# MCU_ZC-ST4X-A005A.net
KiCad netlist of a schematic drawn in Altium Designer
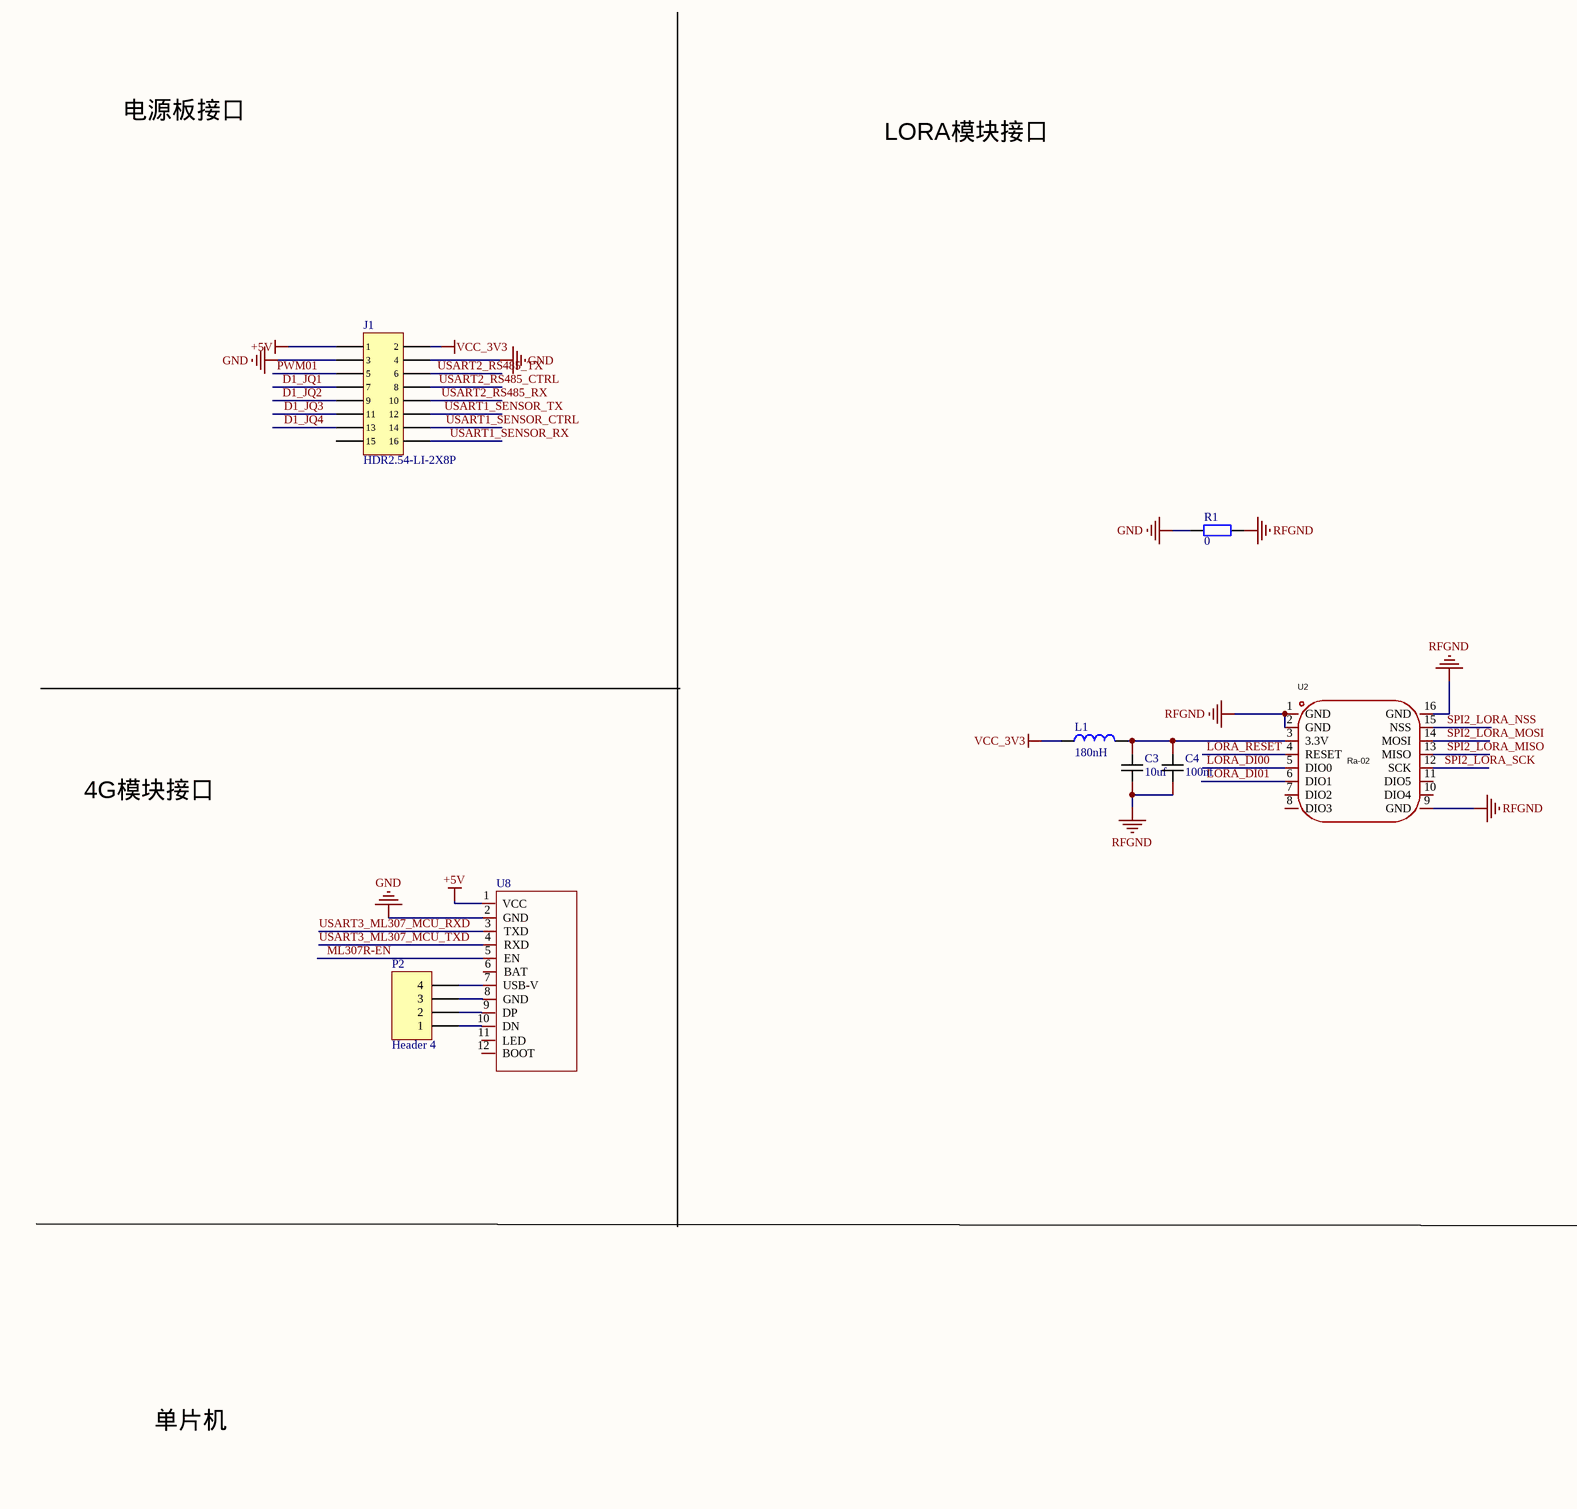
[diagram p0: MCU(ZC-ST4X-A005A).SchDoc, top left]
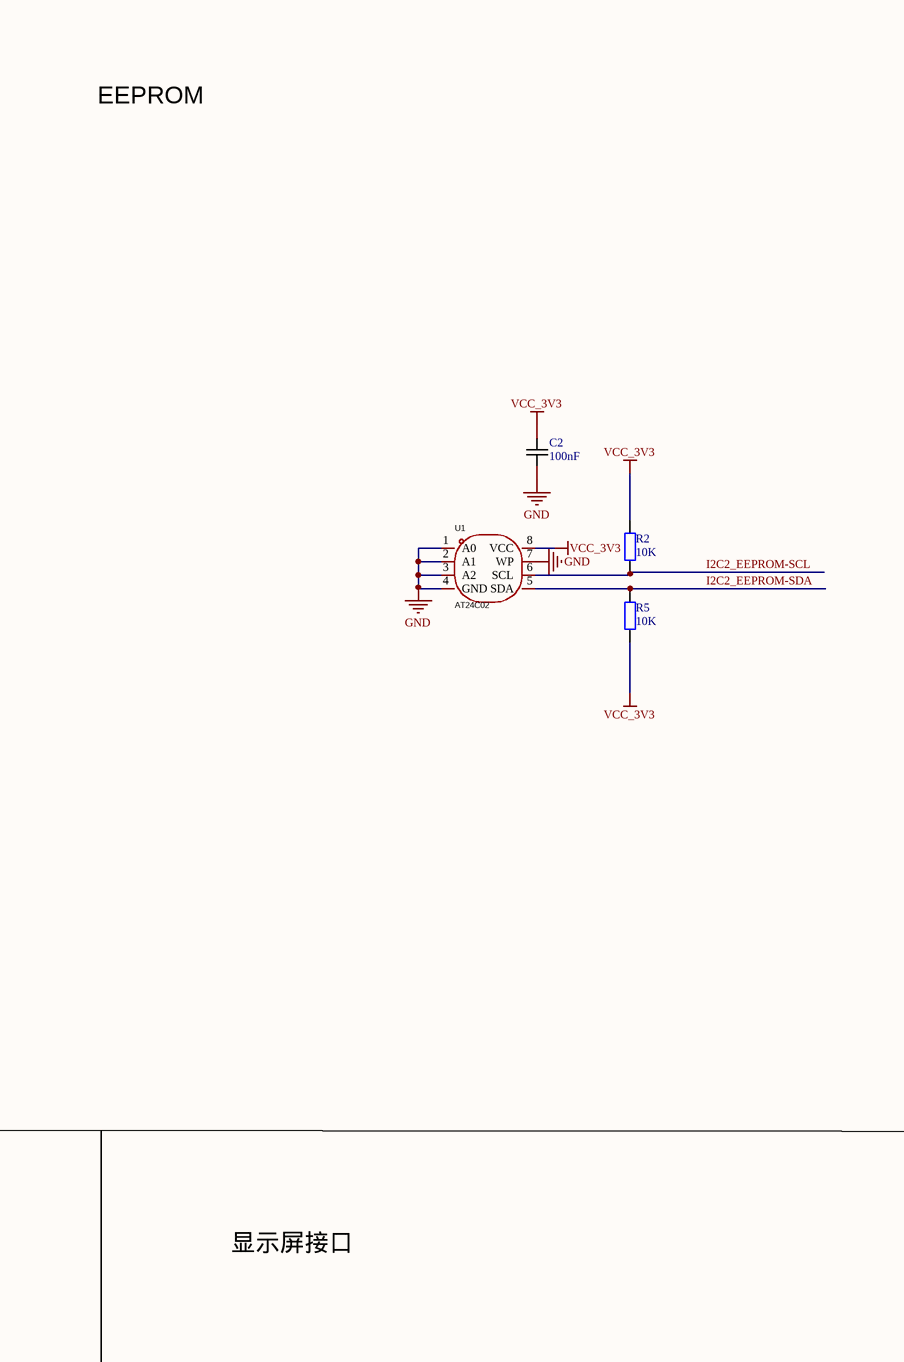
[diagram p1: MCU(ZC-ST4X-A005A).SchDoc, top middle]
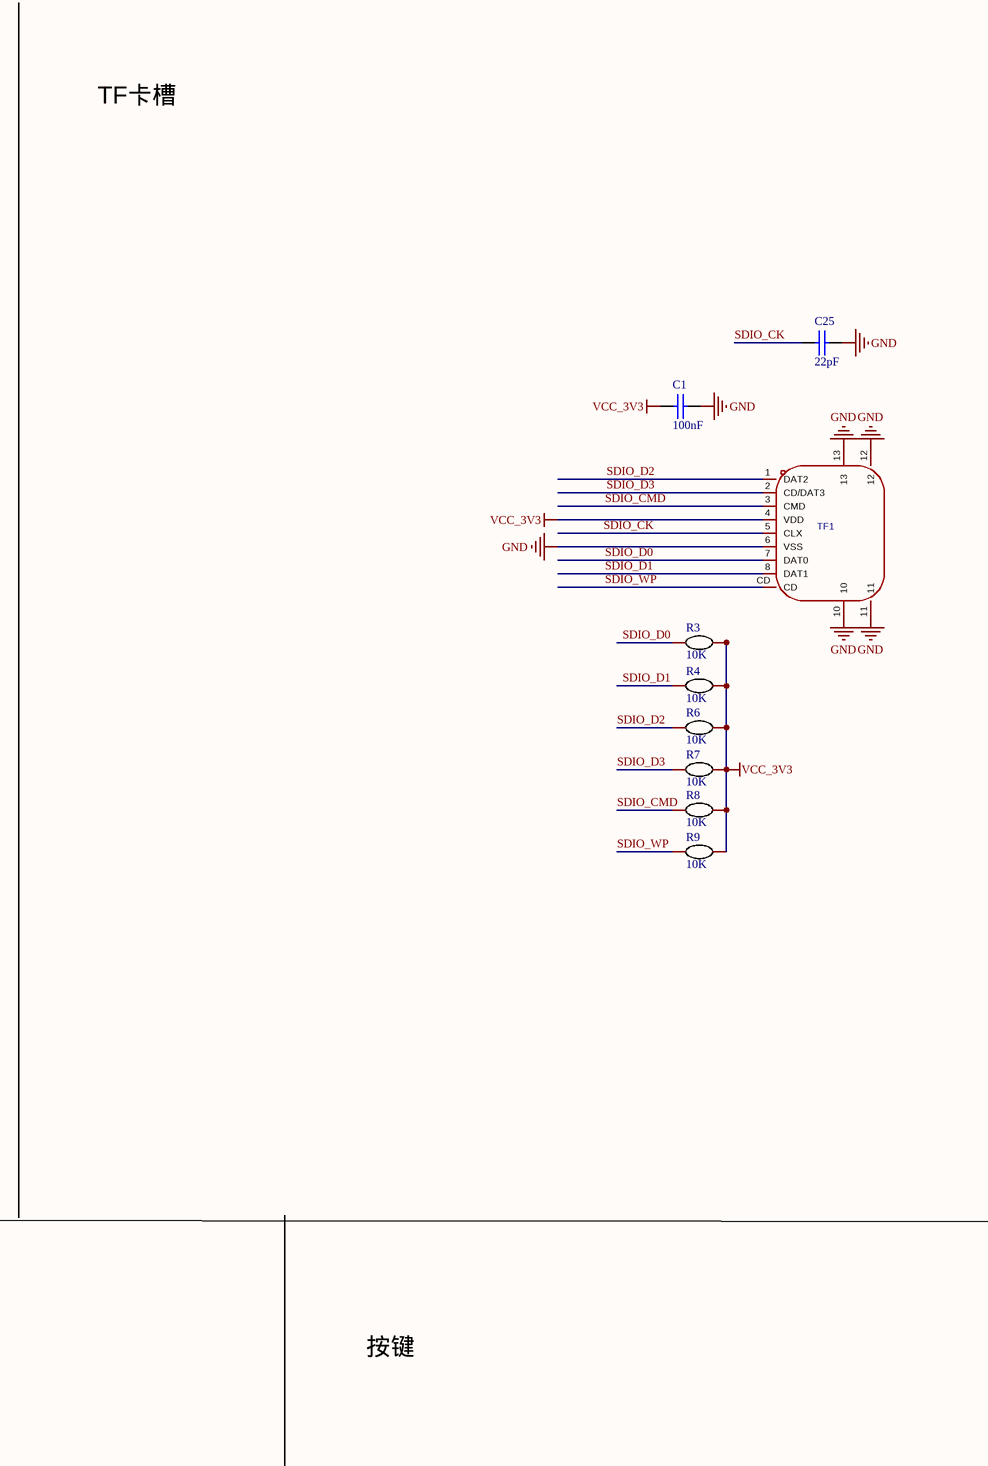
[diagram p2: MCU(ZC-ST4X-A005A).SchDoc, top right]
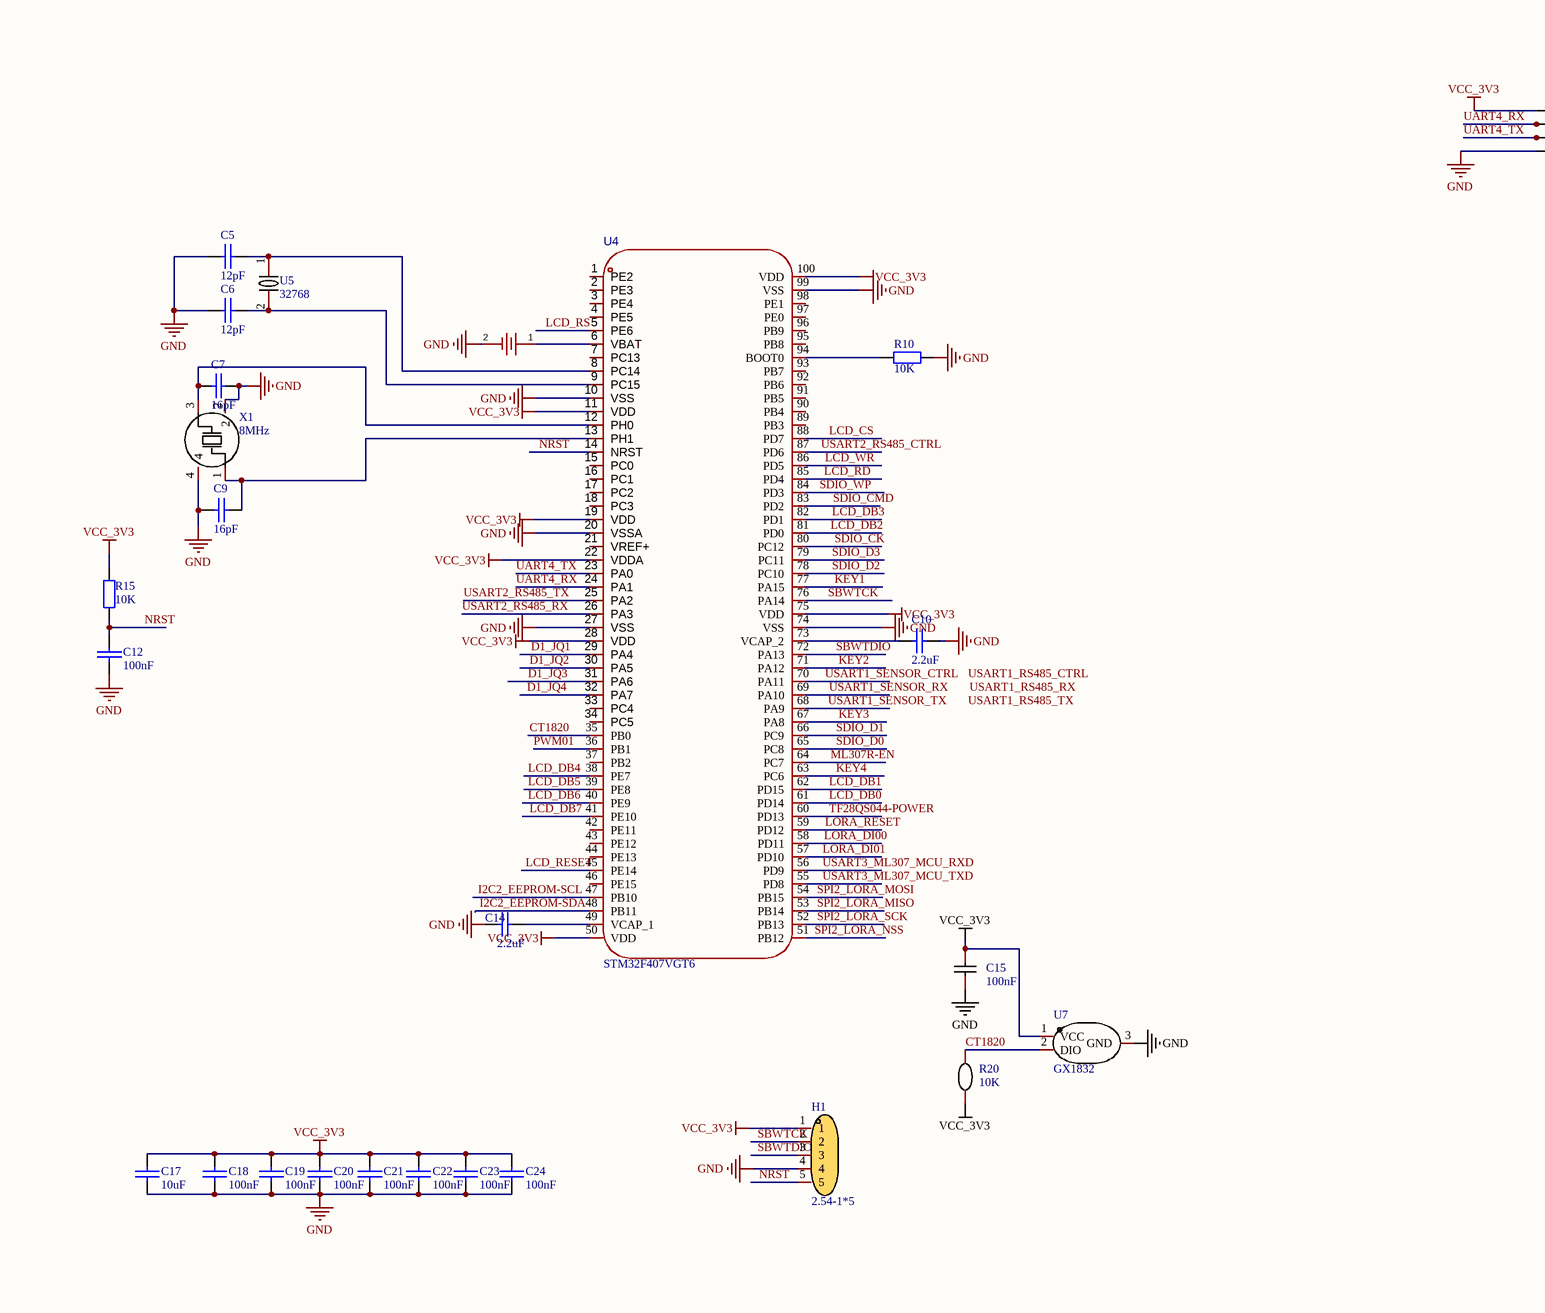
[diagram p3: MCU(ZC-ST4X-A005A).SchDoc, bottom left]
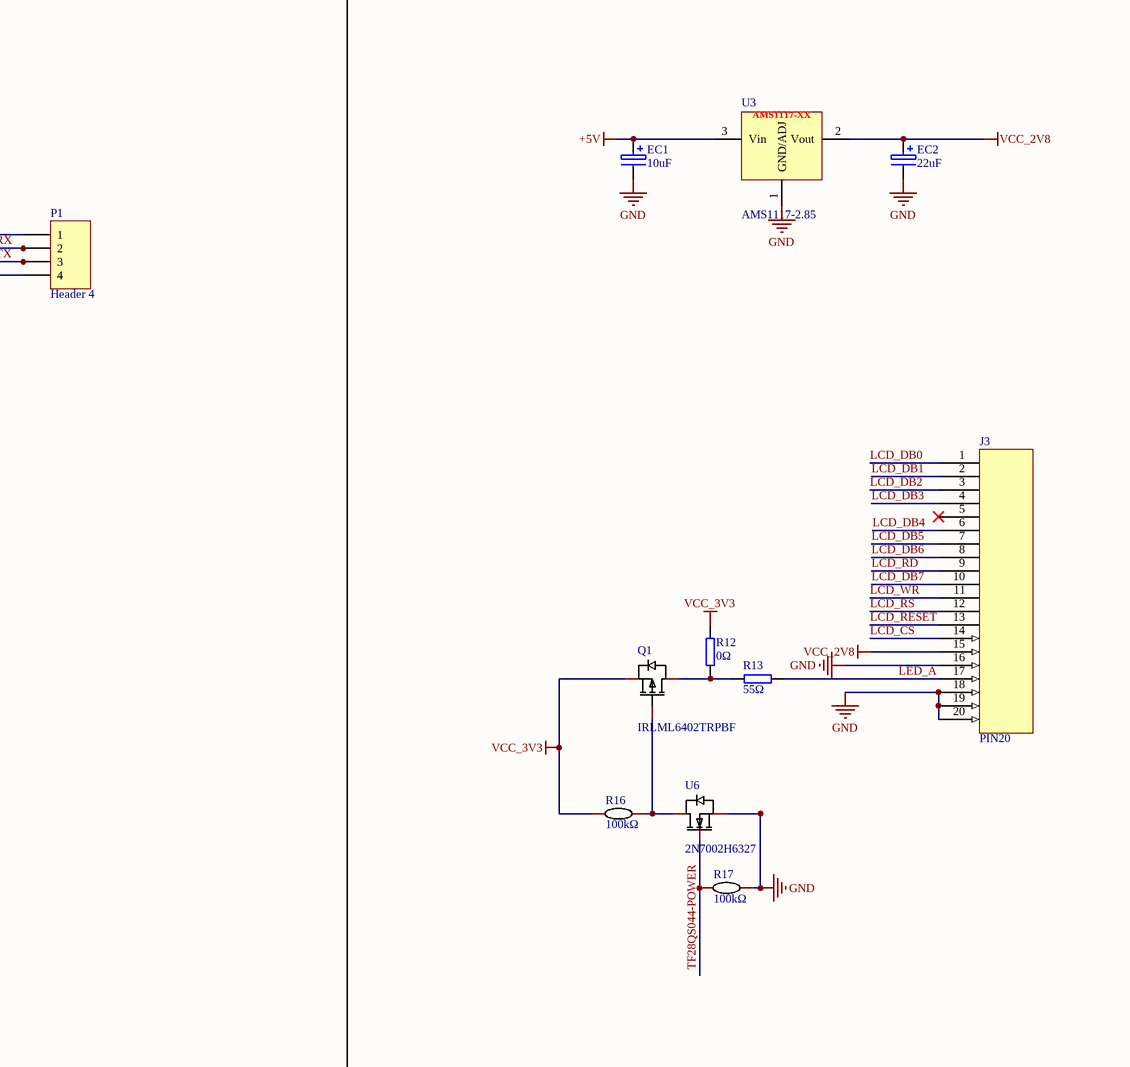
[diagram p4: MCU(ZC-ST4X-A005A).SchDoc, bottom middle]
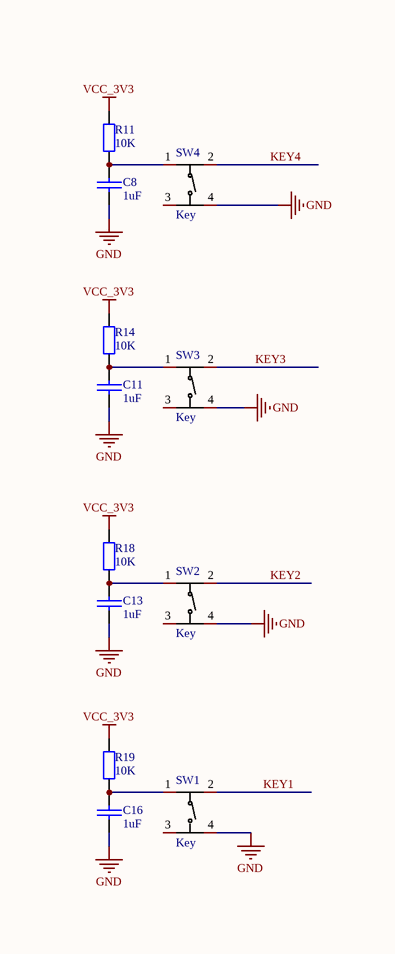
[diagram p5: MCU(ZC-ST4X-A005A).SchDoc, bottom right]

(export (version "E")
  (design (tool "Eeschema 10.0.6"))
  (components
    (comp (ref "BAT1")
      (value "KH-CR2032-2-1")
      (footprint "BAT-TH_CR2032-BS-6-1")
      (libsource (lib "altium-import") (part "root_0_KH-CR2032-2-1_"))
    )
    (comp (ref "C1")
      (value "100nF")
      (footprint "C-0603")
      (description "电容")
      (libsource (lib "泰开常用器件") (part "C普通电容"))
    )
    (comp (ref "C2")
      (value "100nF")
      (footprint "C-0603")
      (fields
        (field (name "MANUFACTURER") "FH(风华)")
        (field (name "MANUFACTURER PART") "0805B104K500NT")
        (field (name "TOLERANCE") "±10%")
      )
      (libsource (lib "altium-import") (part "root_1_0805B104K500NT_"))
    )
    (comp (ref "C3")
      (value "10uf")
      (footprint "C-0603")
      (fields
        (field (name "MANUFACTURER") "FH(风华)")
        (field (name "MANUFACTURER PART") "0805B104K500NT")
        (field (name "TOLERANCE") "±10%")
      )
      (libsource (lib "altium-import") (part "root_1_0805B104K500NT_"))
    )
    (comp (ref "C4")
      (value "100nf")
      (footprint "C-0603")
      (fields
        (field (name "MANUFACTURER") "FH(风华)")
        (field (name "MANUFACTURER PART") "0805B104K500NT")
        (field (name "TOLERANCE") "±10%")
      )
      (libsource (lib "altium-import") (part "root_1_0805B104K500NT_"))
    )
    (comp (ref "C5")
      (value "12pF")
      (footprint "C-0603")
      (description "电容")
      (libsource (lib "泰开常用器件") (part "C普通电容"))
    )
    (comp (ref "C6")
      (value "12pF")
      (footprint "C-0603")
      (description "电容")
      (libsource (lib "泰开常用器件") (part "C普通电容"))
    )
    (comp (ref "C7")
      (value "16pF")
      (footprint "C-0603")
      (description "电容")
      (libsource (lib "泰开常用器件") (part "C普通电容"))
    )
    (comp (ref "C8")
      (value "1uF")
      (footprint "C-0805")
      (description "电容")
      (libsource (lib "泰开常用器件") (part "C普通电容"))
    )
    (comp (ref "C9")
      (value "16pF")
      (footprint "C-0603")
      (description "电容")
      (libsource (lib "泰开常用器件") (part "C普通电容"))
    )
    (comp (ref "C10")
      (value "2.2uF")
      (footprint "C-0603")
      (description "电容")
      (libsource (lib "泰开常用器件") (part "C普通电容"))
    )
    (comp (ref "C11")
      (value "1uF")
      (footprint "C-0805")
      (description "电容")
      (libsource (lib "泰开常用器件") (part "C普通电容"))
    )
    (comp (ref "C12")
      (value "100nF")
      (footprint "C-0603")
      (description "电容")
      (libsource (lib "泰开常用器件") (part "C普通电容"))
    )
    (comp (ref "C13")
      (value "1uF")
      (footprint "C-0805")
      (description "电容")
      (libsource (lib "泰开常用器件") (part "C普通电容"))
    )
    (comp (ref "C14")
      (value "2.2uF")
      (footprint "C-0603")
      (description "电容")
      (libsource (lib "泰开常用器件") (part "C普通电容"))
    )
    (comp (ref "C15")
      (value "100nF")
      (footprint "C-0603")
      (fields
        (field (name "NAME") "100nF")
        (field (name "MANUFACTURER") "FH(风华)")
        (field (name "MANUFACTURER PART") "0805B104K500NT")
        (field (name "TOLERANCE") "±10%")
      )
      (libsource (lib "") (part "root_1_0805B104K500NT__1"))
    )
    (comp (ref "C16")
      (value "1uF")
      (footprint "C-0805")
      (description "电容")
      (libsource (lib "泰开常用器件") (part "C普通电容"))
    )
    (comp (ref "C17")
      (value "10uF")
      (footprint "C-0603")
      (description "电容")
      (libsource (lib "泰开常用器件") (part "C普通电容"))
    )
    (comp (ref "C18")
      (value "100nF")
      (footprint "C-0603")
      (description "电容")
      (libsource (lib "泰开常用器件") (part "C普通电容"))
    )
    (comp (ref "C19")
      (value "100nF")
      (footprint "C-0603")
      (description "电容")
      (libsource (lib "泰开常用器件") (part "C普通电容"))
    )
    (comp (ref "C20")
      (value "100nF")
      (footprint "C-0603")
      (description "电容")
      (libsource (lib "泰开常用器件") (part "C普通电容"))
    )
    (comp (ref "C21")
      (value "100nF")
      (footprint "C-0603")
      (description "电容")
      (libsource (lib "泰开常用器件") (part "C普通电容"))
    )
    (comp (ref "C22")
      (value "100nF")
      (footprint "C-0603")
      (description "电容")
      (libsource (lib "泰开常用器件") (part "C普通电容"))
    )
    (comp (ref "C23")
      (value "100nF")
      (footprint "C-0603")
      (description "电容")
      (libsource (lib "泰开常用器件") (part "C普通电容"))
    )
    (comp (ref "C24")
      (value "100nF")
      (footprint "C-0603")
      (description "电容")
      (libsource (lib "泰开常用器件") (part "C普通电容"))
    )
    (comp (ref "C25")
      (value "22pF")
      (footprint "C-0603")
      (description "电容")
      (libsource (lib "泰开常用器件") (part "C普通电容"))
    )
    (comp (ref "EC1") (value "10uF") (footprint "C4*H") (libsource (lib "电容") (part "CAP-EC")))
    (comp (ref "EC2") (value "22uF") (footprint "C4*H") (libsource (lib "电容") (part "CAP-EC")))
    (comp (ref "H1")
      (value "2.54-1*5")
      (footprint "HDR-TH_5P-P2.54-V-M")
      (libsource (lib "泰开常用器件(3)") (part "2.54-1*5"))
    )
    (comp (ref "J1")
      (value "HDR2.54-LI-2X8P")
      (footprint "IDC-TH_16P-P2.54_BOOMELE-2X8P")
      (description "直插立式双排针")
      (libsource (lib "排针排母") (part "HDR2.54-LI-2X8P"))
    )
    (comp (ref "J3")
      (value "PIN20")
      (footprint "FPC-SMD_KH-CL0.5-H2.0-18PS")
      (libsource (lib "连接器") (part "PIN20"))
    )
    (comp (ref "L1")
      (value "180nH")
      (footprint "R-0805")
      (description "贴片电感")
      (libsource (lib "电感") (part "0603' 180nH 2% 0.24A 车规"))
    )
    (comp (ref "P1")
      (value "Header 4")
      (footprint "HDR2.54-M-LI-4P")
      (description "Header, 4-Pin")
      (fields (field (name "PUBLISHER") "Altium Limited"))
      (libsource (lib "连接器") (part "Header 4"))
    )
    (comp (ref "P2")
      (value "Header 4")
      (footprint "HDR2.54-M-LI-4P")
      (description "Header, 4-Pin")
      (fields (field (name "PUBLISHER") "Altium Limited"))
      (libsource (lib "") (part "Header 4_1"))
    )
    (comp (ref "Q1")
      (value "IRLML6402TRPBF")
      (footprint "SOT-23-3_L2.9-W1.6-P1.90-LS2.8-BR")
      (fields (field (name "NAME") "IRLML6402TRPBF") (field (name "MANUFACTURER") "Infineon(英飞凌)"))
      (libsource (lib "altium-import") (part "root_1_mirrored_IRLML6402TRPBF_C2593_"))
    )
    (comp (ref "R1")
      (value "0")
      (footprint "R-0805")
      (description "贴片电阻，未编号，未录入华芯元件库，临时封装，包括0201，0402，0603，0805，1206，1210，1812，2010，2512")
      (libsource (lib "") (part "通用电阻_1"))
    )
    (comp (ref "R2")
      (value "10K")
      (footprint "R-0603")
      (description "贴片电阻，未编号，未录入华芯元件库，临时封装，包括0201，0402，0603，0805，1206，1210，1812，2010，2512")
      (libsource (lib "电阻") (part "通用电阻"))
    )
    (comp (ref "R3")
      (value "TPM2S103P110R")
      (footprint "R-0603")
      (fields (field (name "NAME") "10K"))
      (libsource (lib "altium-import") (part "root_0_TPM2S103P110R_"))
    )
    (comp (ref "R4")
      (value "TPM2S103P110R")
      (footprint "R-0603")
      (fields (field (name "NAME") "10K"))
      (libsource (lib "altium-import") (part "root_0_TPM2S103P110R_"))
    )
    (comp (ref "R5")
      (value "10K")
      (footprint "R-0603")
      (description "贴片电阻，未编号，未录入华芯元件库，临时封装，包括0201，0402，0603，0805，1206，1210，1812，2010，2512")
      (libsource (lib "电阻") (part "通用电阻"))
    )
    (comp (ref "R6")
      (value "TPM2S103P110R")
      (footprint "R-0603")
      (fields (field (name "NAME") "10K"))
      (libsource (lib "altium-import") (part "root_0_TPM2S103P110R_"))
    )
    (comp (ref "R7")
      (value "TPM2S103P110R")
      (footprint "R-0603")
      (fields (field (name "NAME") "10K"))
      (libsource (lib "altium-import") (part "root_0_TPM2S103P110R_"))
    )
    (comp (ref "R8")
      (value "TPM2S103P110R")
      (footprint "R-0603")
      (fields (field (name "NAME") "10K"))
      (libsource (lib "altium-import") (part "root_0_TPM2S103P110R_"))
    )
    (comp (ref "R9")
      (value "TPM2S103P110R")
      (footprint "R-0603")
      (fields (field (name "NAME") "10K"))
      (libsource (lib "altium-import") (part "root_0_TPM2S103P110R_"))
    )
    (comp (ref "R10")
      (value "10K")
      (footprint "R-0603")
      (description "电阻")
      (fields (field (name "PUBLISHER") "Altium Limited"))
      (libsource (lib "") (part "RES_1"))
    )
    (comp (ref "R11")
      (value "10K")
      (footprint "R-0805")
      (description "电阻")
      (fields (field (name "PUBLISHER") "Altium Limited"))
      (libsource (lib "泰开常用器件") (part "RES"))
    )
    (comp (ref "R12")
      (value "0Ω")
      (footprint "R-0805")
      (description "0603")
      (libsource (lib "电阻  电位器") (part "RES-SMD"))
    )
    (comp (ref "R13")
      (value "55Ω")
      (footprint "R-0805")
      (description "0603")
      (libsource (lib "电阻  电位器") (part "RES-SMD"))
    )
    (comp (ref "R14")
      (value "10K")
      (footprint "R-0805")
      (description "电阻")
      (fields (field (name "PUBLISHER") "Altium Limited"))
      (libsource (lib "泰开常用器件") (part "RES"))
    )
    (comp (ref "R15")
      (value "10K")
      (footprint "C-0603")
      (description "电阻")
      (fields (field (name "PUBLISHER") "Altium Limited"))
      (libsource (lib "泰开常用器件") (part "RES"))
    )
    (comp (ref "R16")
      (value "100kΩ")
      (footprint "r0805")
      (description "电阻类型:厚膜电阻;阻值:10kΩ;精度:±1%;功率:125mW;温度系数:±100ppm/℃;最大工作电压:150V;工作温度范围:-55℃~+155℃;")
      (fields
        (field (name "NAME") "100kΩ")
        (field (name "MANUFACTURER") "UNI-ROYAL(厚声)")
        (field (name "MANUFACTURER PART") "0805W8F1002T5E")
      )
      (libsource (lib "altium-import") (part "root_2_0805W8F1002T5E_C17414_"))
    )
    (comp (ref "R17")
      (value "100kΩ")
      (footprint "r0805")
      (description "电阻类型:厚膜电阻;阻值:10kΩ;精度:±1%;功率:125mW;温度系数:±100ppm/℃;最大工作电压:150V;工作温度范围:-55℃~+155℃;")
      (fields
        (field (name "NAME") "100kΩ")
        (field (name "MANUFACTURER") "UNI-ROYAL(厚声)")
        (field (name "MANUFACTURER PART") "0805W8F1002T5E")
      )
      (libsource (lib "altium-import") (part "root_2_0805W8F1002T5E_C17414_"))
    )
    (comp (ref "R18")
      (value "10K")
      (footprint "R-0805")
      (description "电阻")
      (fields (field (name "PUBLISHER") "Altium Limited"))
      (libsource (lib "泰开常用器件") (part "RES"))
    )
    (comp (ref "R19")
      (value "10K")
      (footprint "R-0805")
      (description "电阻")
      (fields (field (name "PUBLISHER") "Altium Limited"))
      (libsource (lib "泰开常用器件") (part "RES"))
    )
    (comp (ref "R20")
      (value "TPM2S103P110R")
      (footprint "R-0603")
      (fields (field (name "NAME") "10K"))
      (libsource (lib "altium-import") (part "root_1_TPM2S103P110R_"))
    )
    (comp (ref "SW1") (value "Key") (footprint "12X12轻触按键") (libsource (lib "泰开常用器件") (part "Key")))
    (comp (ref "SW2") (value "Key") (footprint "12X12轻触按键") (libsource (lib "泰开常用器件") (part "Key")))
    (comp (ref "SW3") (value "Key") (footprint "12X12轻触按键") (libsource (lib "泰开常用器件") (part "Key")))
    (comp (ref "SW4") (value "Key") (footprint "12X12轻触按键") (libsource (lib "泰开常用器件") (part "Key")))
    (comp (ref "TF1")
      (value "TF-012")
      (footprint "TF-SMD_TF-012")
      (libsource (lib "altium-import") (part "root_0_TF-012_"))
    )
    (comp (ref "U1")
      (value "AT24C02")
      (footprint "SOIC-8")
      (fields (field (name "MANUFACTURER") "IDCHIP(英锐芯)"))
      (libsource (lib "altium-import") (part "root_0_AT24C02_C688857_"))
    )
    (comp (ref "U2")
      (value "Ra-02")
      (footprint "WIRELM-SMD_RA-02-BL")
      (fields (field (name "MANUFACTURER") "Ai-Thinker(安信可)"))
      (libsource (lib "altium-import") (part "root_0_Ra-02_C90039_"))
    )
    (comp (ref "U3")
      (value "AMS1117-2.85")
      (footprint "SOT-223-4")
      (description "AMS   800mA LOW DROPOUT VOLTAGE REGULATOR")
      (libsource (lib "电源管理") (part "AMS1117-XX"))
    )
    (comp (ref "U4")
      (value "STM32F407VGT6")
      (footprint "LQFP-100_L14.0-W14.0-P0.50-LS16.0-BL")
      (libsource (lib "单片机") (part "STM32F407VGT6"))
    )
    (comp (ref "U5")
      (value "32768")
      (footprint "CRYSTAL-SMD_L3.2-W1.5")
      (libsource (lib "泰开常用器件") (part "7N032768NW2"))
    )
    (comp (ref "U6")
      (value "2N7002H6327")
      (footprint "PG-SOT23-3_L2.9-W1.3-P1.90-LS2.4-BR")
      (fields (field (name "NAME") "2N7002H6327") (field (name "MANUFACTURER") "Infineon(英飞凌)"))
      (libsource (lib "altium-import") (part "root_1_2N7002 H6327_"))
    )
    (comp (ref "U7")
      (value "CT1720KR")
      (footprint "SOT-23-3")
      (fields (field (name "NAME") "GX1832") (field (name "MANUFACTURER") "SENSYLINK(申矽凌)"))
      (libsource (lib "altium-import") (part "root_0_CT1720KR_"))
    )
    (comp (ref "U8") (value "U8") (footprint "4G") (libsource (lib "模块") (part "4G(ML307R)")))
    (comp (ref "X1")
      (value "8MHz")
      (footprint "CRYSTAL-SMD_4P-L3.2-W2.5-BL")
      (libsource (lib "泰开常用器件") (part "无源晶振"))
    )
  )
  (nets
    (net (code "1") (name "+5V") (class "Default")
      (node (ref "EC1") (pin "1") (pinfunction "1_1") (pintype "passive"))
      (node (ref "J1") (pin "1") (pinfunction "1_1") (pintype "passive"))
      (node (ref "U3") (pin "3") (pinfunction "Vin_3") (pintype "passive"))
      (node (ref "U8") (pin "1") (pinfunction "VCC_1") (pintype "passive"))
    )
    (net (code "2") (name "/CT1820") (class "Default")
      (node (ref "R20") (pin "2") (pinfunction "2_2") (pintype "passive"))
      (node (ref "U4") (pin "35") (pinfunction "PB0_35") (pintype "passive"))
      (node (ref "U7") (pin "2") (pinfunction "DIO_2") (pintype "passive"))
    )
    (net (code "3") (name "/D1_JQ1") (class "Default")
      (node (ref "J1") (pin "7") (pinfunction "7_7") (pintype "passive"))
      (node (ref "U4") (pin "29") (pinfunction "PA4_29") (pintype "passive"))
    )
    (net (code "4") (name "/D1_JQ2") (class "Default")
      (node (ref "J1") (pin "9") (pinfunction "9_9") (pintype "passive"))
      (node (ref "U4") (pin "30") (pinfunction "PA5_30") (pintype "passive"))
    )
    (net (code "5") (name "/D1_JQ3") (class "Default")
      (node (ref "J1") (pin "11") (pinfunction "11_11") (pintype "passive"))
      (node (ref "U4") (pin "31") (pinfunction "PA6_31") (pintype "passive"))
    )
    (net (code "6") (name "/D1_JQ4") (class "Default")
      (node (ref "J1") (pin "13") (pinfunction "13_13") (pintype "passive"))
      (node (ref "U4") (pin "32") (pinfunction "PA7_32") (pintype "passive"))
    )
    (net (code "7") (name "/I2C2_EEPROM-SCL") (class "Default")
      (node (ref "R2") (pin "1") (pinfunction "1_1") (pintype "passive"))
      (node (ref "U1") (pin "6") (pinfunction "SCL_6") (pintype "passive"))
      (node (ref "U4") (pin "47") (pinfunction "PB10_47") (pintype "passive"))
    )
    (net (code "8") (name "/I2C2_EEPROM-SDA") (class "Default")
      (node (ref "R5") (pin "2") (pinfunction "2_2") (pintype "passive"))
      (node (ref "U1") (pin "5") (pinfunction "SDA_5") (pintype "passive"))
      (node (ref "U4") (pin "48") (pinfunction "PB11_48") (pintype "passive"))
    )
    (net (code "9") (name "/KEY1") (class "Default")
      (node (ref "SW1") (pin "2") (pinfunction "2_2") (pintype "passive"))
      (node (ref "U4") (pin "77") (pinfunction "PA15_77") (pintype "passive"))
    )
    (net (code "10") (name "/KEY2") (class "Default")
      (node (ref "SW2") (pin "2") (pinfunction "2_2") (pintype "passive"))
      (node (ref "U4") (pin "71") (pinfunction "PA12_71") (pintype "passive"))
    )
    (net (code "11") (name "/KEY3") (class "Default")
      (node (ref "SW3") (pin "2") (pinfunction "2_2") (pintype "passive"))
      (node (ref "U4") (pin "67") (pinfunction "PA8_67") (pintype "passive"))
    )
    (net (code "12") (name "/KEY4") (class "Default")
      (node (ref "SW4") (pin "2") (pinfunction "2_2") (pintype "passive"))
      (node (ref "U4") (pin "63") (pinfunction "PC6_63") (pintype "passive"))
    )
    (net (code "13") (name "/LCD_CS") (class "Default")
      (node (ref "J3") (pin "14") (pinfunction "14_14") (pintype "input"))
      (node (ref "U4") (pin "88") (pinfunction "PD7_88") (pintype "passive"))
    )
    (net (code "14") (name "/LCD_DB0") (class "Default")
      (node (ref "J3") (pin "1") (pintype "passive"))
      (node (ref "U4") (pin "61") (pinfunction "PD14_61") (pintype "passive"))
    )
    (net (code "15") (name "/LCD_DB1") (class "Default")
      (node (ref "J3") (pin "2") (pintype "passive"))
      (node (ref "U4") (pin "62") (pinfunction "PD15_62") (pintype "passive"))
    )
    (net (code "16") (name "/LCD_DB2") (class "Default")
      (node (ref "J3") (pin "3") (pintype "passive"))
      (node (ref "U4") (pin "81") (pinfunction "PD0_81") (pintype "passive"))
    )
    (net (code "17") (name "/LCD_DB3") (class "Default")
      (node (ref "J3") (pin "4") (pintype "passive"))
      (node (ref "U4") (pin "82") (pinfunction "PD1_82") (pintype "passive"))
    )
    (net (code "18") (name "/LCD_DB4") (class "Default")
      (node (ref "J3") (pin "6") (pintype "passive"))
      (node (ref "U4") (pin "38") (pinfunction "PE7_38") (pintype "passive"))
    )
    (net (code "19") (name "/LCD_DB5") (class "Default")
      (node (ref "J3") (pin "7") (pintype "passive"))
      (node (ref "U4") (pin "39") (pinfunction "PE8_39") (pintype "passive"))
    )
    (net (code "20") (name "/LCD_DB6") (class "Default")
      (node (ref "J3") (pin "8") (pintype "passive"))
      (node (ref "U4") (pin "40") (pinfunction "PE9_40") (pintype "passive"))
    )
    (net (code "21") (name "/LCD_DB7") (class "Default")
      (node (ref "J3") (pin "10") (pintype "passive"))
      (node (ref "U4") (pin "41") (pinfunction "PE10_41") (pintype "passive"))
    )
    (net (code "22") (name "/LCD_RD") (class "Default")
      (node (ref "J3") (pin "9") (pintype "passive"))
      (node (ref "U4") (pin "85") (pinfunction "PD4_85") (pintype "passive"))
    )
    (net (code "23") (name "/LCD_RESET") (class "Default")
      (node (ref "J3") (pin "13") (pinfunction "13_13") (pintype "passive"))
      (node (ref "U4") (pin "45") (pinfunction "PE14_45") (pintype "passive"))
    )
    (net (code "24") (name "/LCD_RS") (class "Default")
      (node (ref "J3") (pin "12") (pinfunction "12_12") (pintype "passive"))
      (node (ref "U4") (pin "5") (pinfunction "PE6_5") (pintype "passive"))
    )
    (net (code "25") (name "/LCD_WR") (class "Default")
      (node (ref "J3") (pin "11") (pinfunction "11_11") (pintype "passive"))
      (node (ref "U4") (pin "86") (pinfunction "PD5_86") (pintype "passive"))
    )
    (net (code "26") (name "/LED_A") (class "Default")
      (node (ref "J3") (pin "17") (pinfunction "17_17") (pintype "input"))
      (node (ref "R13") (pin "1") (pinfunction "1_1") (pintype "passive"))
    )
    (net (code "27") (name "/LORA_DI00") (class "Default")
      (node (ref "U2") (pin "5") (pinfunction "DIO0_5") (pintype "passive"))
      (node (ref "U4") (pin "58") (pinfunction "PD11_58") (pintype "passive"))
    )
    (net (code "28") (name "/LORA_DI01") (class "Default")
      (node (ref "U2") (pin "6") (pinfunction "DIO1_6") (pintype "passive"))
      (node (ref "U4") (pin "57") (pinfunction "PD10_57") (pintype "passive"))
    )
    (net (code "29") (name "/LORA_RESET") (class "Default")
      (node (ref "U2") (pin "4") (pinfunction "RESET_4") (pintype "passive"))
      (node (ref "U4") (pin "59") (pinfunction "PD12_59") (pintype "passive"))
    )
    (net (code "30") (name "/ML307R-EN") (class "Default")
      (node (ref "U4") (pin "64") (pinfunction "PC7_64") (pintype "passive"))
      (node (ref "U8") (pin "5") (pinfunction "EN_5") (pintype "passive"))
    )
    (net (code "31") (name "/NRST") (class "Default")
      (node (ref "C12") (pin "2") (pinfunction "2_2") (pintype "passive"))
      (node (ref "H1") (pin "5") (pinfunction "5_5") (pintype "passive"))
      (node (ref "R15") (pin "1") (pinfunction "1_1") (pintype "passive"))
      (node (ref "U4") (pin "14") (pinfunction "NRST_14") (pintype "passive"))
    )
    (net (code "32") (name "/PWM01") (class "Default")
      (node (ref "J1") (pin "5") (pinfunction "5_5") (pintype "passive"))
      (node (ref "U4") (pin "36") (pinfunction "PB1_36") (pintype "passive"))
    )
    (net (code "33") (name "/SBWTCK") (class "Default")
      (node (ref "H1") (pin "2") (pinfunction "2_2") (pintype "passive"))
      (node (ref "U4") (pin "76") (pinfunction "PA14_76") (pintype "passive"))
    )
    (net (code "34") (name "/SBWTDIO") (class "Default")
      (node (ref "H1") (pin "3") (pinfunction "3_3") (pintype "passive"))
      (node (ref "U4") (pin "72") (pinfunction "PA13_72") (pintype "passive"))
    )
    (net (code "35") (name "/SDIO_CK") (class "Default")
      (node (ref "C25") (pin "1") (pinfunction "1_1") (pintype "passive"))
      (node (ref "TF1") (pin "5") (pinfunction "CLX_5") (pintype "passive"))
      (node (ref "U4") (pin "80") (pinfunction "PC12_80") (pintype "passive"))
    )
    (net (code "36") (name "/SDIO_CMD") (class "Default")
      (node (ref "R8") (pin "1") (pinfunction "1_1") (pintype "passive"))
      (node (ref "TF1") (pin "3") (pinfunction "CMD_3") (pintype "passive"))
      (node (ref "U4") (pin "83") (pinfunction "PD2_83") (pintype "passive"))
    )
    (net (code "37") (name "/SDIO_D0") (class "Default")
      (node (ref "R3") (pin "1") (pinfunction "1_1") (pintype "passive"))
      (node (ref "TF1") (pin "7") (pinfunction "DAT0_7") (pintype "passive"))
      (node (ref "U4") (pin "65") (pinfunction "PC8_65") (pintype "passive"))
    )
    (net (code "38") (name "/SDIO_D1") (class "Default")
      (node (ref "R4") (pin "1") (pinfunction "1_1") (pintype "passive"))
      (node (ref "TF1") (pin "8") (pinfunction "DAT1_8") (pintype "passive"))
      (node (ref "U4") (pin "66") (pinfunction "PC9_66") (pintype "passive"))
    )
    (net (code "39") (name "/SDIO_D2") (class "Default")
      (node (ref "R6") (pin "1") (pinfunction "1_1") (pintype "passive"))
      (node (ref "TF1") (pin "1") (pinfunction "DAT2_1") (pintype "passive"))
      (node (ref "U4") (pin "78") (pinfunction "PC10_78") (pintype "passive"))
    )
    (net (code "40") (name "/SDIO_D3") (class "Default")
      (node (ref "R7") (pin "1") (pinfunction "1_1") (pintype "passive"))
      (node (ref "TF1") (pin "2") (pinfunction "CD/DAT3_2") (pintype "passive"))
      (node (ref "U4") (pin "79") (pinfunction "PC11_79") (pintype "passive"))
    )
    (net (code "41") (name "/SDIO_WP") (class "Default")
      (node (ref "R9") (pin "1") (pinfunction "1_1") (pintype "passive"))
      (node (ref "TF1") (pin "CD") (pinfunction "CD_CD") (pintype "passive"))
      (node (ref "U4") (pin "84") (pinfunction "PD3_84") (pintype "passive"))
    )
    (net (code "42") (name "/SPI2_LORA_MISO") (class "Default")
      (node (ref "U2") (pin "13") (pinfunction "MISO_13") (pintype "passive"))
      (node (ref "U4") (pin "53") (pinfunction "PB14_53") (pintype "passive"))
    )
    (net (code "43") (name "/SPI2_LORA_MOSI") (class "Default")
      (node (ref "U2") (pin "14") (pinfunction "MOSI_14") (pintype "passive"))
      (node (ref "U4") (pin "54") (pinfunction "PB15_54") (pintype "passive"))
    )
    (net (code "44") (name "/SPI2_LORA_NSS") (class "Default")
      (node (ref "U2") (pin "15") (pinfunction "NSS_15") (pintype "passive"))
      (node (ref "U4") (pin "51") (pinfunction "PB12_51") (pintype "passive"))
    )
    (net (code "45") (name "/SPI2_LORA_SCK") (class "Default")
      (node (ref "U2") (pin "12") (pinfunction "SCK_12") (pintype "passive"))
      (node (ref "U4") (pin "52") (pinfunction "PB13_52") (pintype "passive"))
    )
    (net (code "46") (name "/TF28QS044-POWER") (class "Default")
      (node (ref "R17") (pin "2") (pinfunction "2_2") (pintype "passive"))
      (node (ref "U4") (pin "60") (pinfunction "PD13_60") (pintype "passive"))
      (node (ref "U6") (pin "1") (pinfunction "G_1") (pintype "passive"))
    )
    (net (code "47") (name "/UART4_RX") (class "Default")
      (node (ref "P1") (pin "2") (pinfunction "2_2") (pintype "passive"))
      (node (ref "U4") (pin "24") (pinfunction "PA1_24") (pintype "passive"))
    )
    (net (code "48") (name "/UART4_TX") (class "Default")
      (node (ref "P1") (pin "3") (pinfunction "3_3") (pintype "passive"))
      (node (ref "U4") (pin "23") (pinfunction "PA0_23") (pintype "passive"))
    )
    (net (code "52") (name "/USART1_SENSOR_CTRL") (class "Default")
      (node (ref "J1") (pin "14") (pinfunction "14_14") (pintype "passive"))
      (node (ref "U4") (pin "70") (pinfunction "PA11_70") (pintype "passive"))
    )
    (net (code "53") (name "/USART1_SENSOR_RX") (class "Default")
      (node (ref "J1") (pin "16") (pinfunction "16_16") (pintype "passive"))
      (node (ref "U4") (pin "69") (pinfunction "PA10_69") (pintype "passive"))
    )
    (net (code "54") (name "/USART1_SENSOR_TX") (class "Default")
      (node (ref "J1") (pin "12") (pinfunction "12_12") (pintype "passive"))
      (node (ref "U4") (pin "68") (pinfunction "PA9_68") (pintype "passive"))
    )
    (net (code "55") (name "/USART2_RS485_CTRL") (class "Default")
      (node (ref "J1") (pin "8") (pinfunction "8_8") (pintype "passive"))
      (node (ref "U4") (pin "87") (pinfunction "PD6_87") (pintype "passive"))
    )
    (net (code "56") (name "/USART2_RS485_RX") (class "Default")
      (node (ref "J1") (pin "10") (pinfunction "10_10") (pintype "passive"))
      (node (ref "U4") (pin "26") (pinfunction "PA3_26") (pintype "passive"))
    )
    (net (code "57") (name "/USART2_RS485_TX") (class "Default")
      (node (ref "J1") (pin "6") (pinfunction "6_6") (pintype "passive"))
      (node (ref "U4") (pin "25") (pinfunction "PA2_25") (pintype "passive"))
    )
    (net (code "58") (name "/USART3_ML307_MCU_RXD") (class "Default")
      (node (ref "U4") (pin "56") (pinfunction "PD9_56") (pintype "passive"))
      (node (ref "U8") (pin "3") (pinfunction "TXD_3") (pintype "passive"))
    )
    (net (code "59") (name "/USART3_ML307_MCU_TXD") (class "Default")
      (node (ref "U4") (pin "55") (pinfunction "PD8_55") (pintype "passive"))
      (node (ref "U8") (pin "4") (pinfunction "RXD_4") (pintype "passive"))
    )
    (net (code "60") (name "GND") (class "Default")
      (node (ref "BAT1") (pin "2") (pinfunction "2_2") (pintype "passive"))
      (node (ref "C1") (pin "1") (pinfunction "1_1") (pintype "passive"))
      (node (ref "C10") (pin "1") (pinfunction "1_1") (pintype "passive"))
      (node (ref "C11") (pin "1") (pinfunction "1_1") (pintype "passive"))
      (node (ref "C12") (pin "1") (pinfunction "1_1") (pintype "passive"))
      (node (ref "C13") (pin "1") (pinfunction "1_1") (pintype "passive"))
      (node (ref "C14") (pin "1") (pinfunction "1_1") (pintype "passive"))
      (node (ref "C15") (pin "1") (pinfunction "1_1") (pintype "passive"))
      (node (ref "C16") (pin "1") (pinfunction "1_1") (pintype "passive"))
      (node (ref "C17") (pin "1") (pinfunction "1_1") (pintype "passive"))
      (node (ref "C18") (pin "1") (pinfunction "1_1") (pintype "passive"))
      (node (ref "C19") (pin "1") (pinfunction "1_1") (pintype "passive"))
      (node (ref "C2") (pin "1") (pinfunction "1_1") (pintype "passive"))
      (node (ref "C20") (pin "1") (pinfunction "1_1") (pintype "passive"))
      (node (ref "C21") (pin "1") (pinfunction "1_1") (pintype "passive"))
      (node (ref "C22") (pin "1") (pinfunction "1_1") (pintype "passive"))
      (node (ref "C23") (pin "1") (pinfunction "1_1") (pintype "passive"))
      (node (ref "C24") (pin "1") (pinfunction "1_1") (pintype "passive"))
      (node (ref "C25") (pin "2") (pinfunction "2_2") (pintype "passive"))
      (node (ref "C5") (pin "1") (pinfunction "1_1") (pintype "passive"))
      (node (ref "C6") (pin "1") (pinfunction "1_1") (pintype "passive"))
      (node (ref "C7") (pin "1") (pinfunction "1_1") (pintype "passive"))
      (node (ref "C8") (pin "1") (pinfunction "1_1") (pintype "passive"))
      (node (ref "C9") (pin "2") (pinfunction "2_2") (pintype "passive"))
      (node (ref "EC1") (pin "2") (pinfunction "2_2") (pintype "passive"))
      (node (ref "EC2") (pin "2") (pinfunction "2_2") (pintype "passive"))
      (node (ref "H1") (pin "4") (pinfunction "4_4") (pintype "passive"))
      (node (ref "J1") (pin "3") (pinfunction "3_3") (pintype "passive"))
      (node (ref "J1") (pin "4") (pinfunction "4_4") (pintype "passive"))
      (node (ref "J3") (pin "16") (pinfunction "16_16") (pintype "input"))
      (node (ref "J3") (pin "18") (pinfunction "18_18") (pintype "input"))
      (node (ref "J3") (pin "19") (pinfunction "19_19") (pintype "input"))
      (node (ref "J3") (pin "20") (pinfunction "20_20") (pintype "input"))
      (node (ref "P1") (pin "4") (pinfunction "4_4") (pintype "passive"))
      (node (ref "R1") (pin "1") (pinfunction "1_1") (pintype "passive"))
      (node (ref "R10") (pin "1") (pinfunction "1_1") (pintype "passive"))
      (node (ref "R17") (pin "1") (pinfunction "1_1") (pintype "passive"))
      (node (ref "SW1") (pin "4") (pinfunction "4_4") (pintype "passive"))
      (node (ref "SW2") (pin "4") (pinfunction "4_4") (pintype "passive"))
      (node (ref "SW3") (pin "4") (pinfunction "4_4") (pintype "passive"))
      (node (ref "SW4") (pin "4") (pinfunction "4_4") (pintype "passive"))
      (node (ref "TF1") (pin "10") (pinfunction "10_10") (pintype "passive"))
      (node (ref "TF1") (pin "11") (pinfunction "11_11") (pintype "passive"))
      (node (ref "TF1") (pin "12") (pinfunction "12_12") (pintype "passive"))
      (node (ref "TF1") (pin "13") (pinfunction "13_13") (pintype "passive"))
      (node (ref "TF1") (pin "6") (pinfunction "VSS_6") (pintype "passive"))
      (node (ref "U1") (pin "1") (pinfunction "A0_1") (pintype "passive"))
      (node (ref "U1") (pin "2") (pinfunction "A1_2") (pintype "passive"))
      (node (ref "U1") (pin "3") (pinfunction "A2_3") (pintype "passive"))
      (node (ref "U1") (pin "4") (pinfunction "GND_4") (pintype "passive"))
      (node (ref "U1") (pin "7") (pinfunction "WP_7") (pintype "passive"))
      (node (ref "U3") (pin "1") (pinfunction "GND/ADJ_1") (pintype "passive"))
      (node (ref "U4") (pin "10") (pinfunction "VSS_10") (pintype "passive"))
      (node (ref "U4") (pin "20") (pinfunction "VSSA_20") (pintype "passive"))
      (node (ref "U4") (pin "27") (pinfunction "VSS_27") (pintype "passive"))
      (node (ref "U4") (pin "74") (pinfunction "VSS_74") (pintype "passive"))
      (node (ref "U4") (pin "99") (pinfunction "VSS_99") (pintype "passive"))
      (node (ref "U6") (pin "2") (pinfunction "S_2") (pintype "passive"))
      (node (ref "U7") (pin "3") (pinfunction "GND_3") (pintype "passive"))
      (node (ref "U8") (pin "2") (pinfunction "GND_2") (pintype "passive"))
      (node (ref "X1") (pin "2") (pinfunction "2_2") (pintype "passive"))
      (node (ref "X1") (pin "4") (pinfunction "4_4") (pintype "passive"))
    )
    (net (code "61") (name "Net-(C8-Pad2)") (class "Default")
      (node (ref "C8") (pin "2") (pinfunction "2_2") (pintype "passive"))
      (node (ref "R11") (pin "1") (pinfunction "1_1") (pintype "passive"))
      (node (ref "SW4") (pin "1") (pinfunction "1_1") (pintype "passive"))
    )
    (net (code "62") (name "Net-(C11-Pad2)") (class "Default")
      (node (ref "C11") (pin "2") (pinfunction "2_2") (pintype "passive"))
      (node (ref "R14") (pin "1") (pinfunction "1_1") (pintype "passive"))
      (node (ref "SW3") (pin "1") (pinfunction "1_1") (pintype "passive"))
    )
    (net (code "63") (name "Net-(C13-Pad2)") (class "Default")
      (node (ref "C13") (pin "2") (pinfunction "2_2") (pintype "passive"))
      (node (ref "R18") (pin "1") (pinfunction "1_1") (pintype "passive"))
      (node (ref "SW2") (pin "1") (pinfunction "1_1") (pintype "passive"))
    )
    (net (code "64") (name "Net-(C16-Pad2)") (class "Default")
      (node (ref "C16") (pin "2") (pinfunction "2_2") (pintype "passive"))
      (node (ref "R19") (pin "1") (pinfunction "1_1") (pintype "passive"))
      (node (ref "SW1") (pin "1") (pinfunction "1_1") (pintype "passive"))
    )
    (net (code "65") (name "Net-(P2-Pad3)") (class "Default")
      (node (ref "P2") (pin "3") (pinfunction "3_3") (pintype "passive"))
      (node (ref "U8") (pin "8") (pinfunction "GND_8") (pintype "passive"))
    )
    (net (code "66") (name "Net-(Q1-D)") (class "Default")
      (node (ref "Q1") (pin "3") (pinfunction "D_3") (pintype "passive"))
      (node (ref "R12") (pin "2") (pinfunction "2_2") (pintype "passive"))
      (node (ref "R13") (pin "2") (pinfunction "2_2") (pintype "passive"))
    )
    (net (code "67") (name "Net-(Q1-G)") (class "Default")
      (node (ref "Q1") (pin "1") (pinfunction "G_1") (pintype "passive"))
      (node (ref "R16") (pin "1") (pinfunction "1_1") (pintype "passive"))
      (node (ref "U6") (pin "3") (pinfunction "D_3") (pintype "passive"))
    )
    (net (code "68") (name "Net-(U2-3.3V)") (class "Default")
      (node (ref "C3") (pin "2") (pinfunction "2_2") (pintype "passive"))
      (node (ref "C4") (pin "2") (pinfunction "2_2") (pintype "passive"))
      (node (ref "L1") (pin "2") (pinfunction "2_2") (pintype "passive"))
      (node (ref "U2") (pin "3") (pinfunction "3.3V_3") (pintype "passive"))
    )
    (net (code "69") (name "Net-(U4-BOOT0)") (class "Default")
      (node (ref "R10") (pin "2") (pinfunction "2_2") (pintype "passive"))
      (node (ref "U4") (pin "94") (pinfunction "BOOT0_94") (pintype "passive"))
    )
    (net (code "70") (name "Net-(U4-PC14)") (class "Default")
      (node (ref "C5") (pin "2") (pinfunction "2_2") (pintype "passive"))
      (node (ref "U4") (pin "8") (pinfunction "PC14_8") (pintype "passive"))
      (node (ref "U5") (pin "1") (pinfunction "1_1") (pintype "passive"))
    )
    (net (code "71") (name "Net-(U4-PC15)") (class "Default")
      (node (ref "C6") (pin "2") (pinfunction "2_2") (pintype "passive"))
      (node (ref "U4") (pin "9") (pinfunction "PC15_9") (pintype "passive"))
      (node (ref "U5") (pin "2") (pinfunction "2_2") (pintype "passive"))
    )
    (net (code "72") (name "Net-(U4-PH0)") (class "Default")
      (node (ref "C7") (pin "2") (pinfunction "2_2") (pintype "passive"))
      (node (ref "U4") (pin "12") (pinfunction "PH0_12") (pintype "passive"))
      (node (ref "X1") (pin "3") (pinfunction "OSC2_3") (pintype "passive"))
    )
    (net (code "73") (name "Net-(U4-PH1)") (class "Default")
      (node (ref "C9") (pin "1") (pinfunction "1_1") (pintype "passive"))
      (node (ref "U4") (pin "13") (pinfunction "PH1_13") (pintype "passive"))
      (node (ref "X1") (pin "1") (pinfunction "OSC1_1") (pintype "passive"))
    )
    (net (code "74") (name "Net-(U4-VBAT)") (class "Default")
      (node (ref "BAT1") (pin "1") (pinfunction "1_1") (pintype "passive"))
      (node (ref "U4") (pin "6") (pinfunction "VBAT_6") (pintype "passive"))
    )
    (net (code "75") (name "Net-(U4-VCAP_1)") (class "Default")
      (node (ref "C14") (pin "2") (pinfunction "2_2") (pintype "passive"))
      (node (ref "U4") (pin "49") (pinfunction "VCAP_1_49") (pintype "passive"))
    )
    (net (code "76") (name "Net-(U4-VCAP_2)") (class "Default")
      (node (ref "C10") (pin "2") (pinfunction "2_2") (pintype "passive"))
      (node (ref "U4") (pin "73") (pinfunction "VCAP_2_73") (pintype "passive"))
    )
    (net (code "77") (name "Net-(U8-DN)") (class "Default")
      (node (ref "P2") (pin "1") (pinfunction "1_1") (pintype "passive"))
      (node (ref "U8") (pin "10") (pinfunction "DN_10") (pintype "passive"))
    )
    (net (code "78") (name "Net-(U8-DP)") (class "Default")
      (node (ref "P2") (pin "2") (pinfunction "2_2") (pintype "passive"))
      (node (ref "U8") (pin "9") (pinfunction "DP_9") (pintype "passive"))
    )
    (net (code "79") (name "Net-(U8-USB-V)") (class "Default")
      (node (ref "P2") (pin "4") (pinfunction "4_4") (pintype "passive"))
      (node (ref "U8") (pin "7") (pinfunction "USB-V_7") (pintype "passive"))
    )
    (net (code "80") (name "RFGND") (class "Default")
      (node (ref "C3") (pin "1") (pinfunction "1_1") (pintype "passive"))
      (node (ref "C4") (pin "1") (pinfunction "1_1") (pintype "passive"))
      (node (ref "R1") (pin "2") (pinfunction "2_2") (pintype "passive"))
      (node (ref "U2") (pin "1") (pinfunction "GND_1") (pintype "passive"))
      (node (ref "U2") (pin "16") (pinfunction "GND_16") (pintype "passive"))
      (node (ref "U2") (pin "2") (pinfunction "GND_2") (pintype "passive"))
      (node (ref "U2") (pin "9") (pinfunction "GND_9") (pintype "passive"))
    )
    (net (code "81") (name "VCC_2V8") (class "Default")
      (node (ref "EC2") (pin "1") (pinfunction "1_1") (pintype "passive"))
      (node (ref "J3") (pin "15") (pinfunction "15_15") (pintype "input"))
      (node (ref "U3") (pin "2") (pinfunction "Vout_2") (pintype "passive"))
    )
    (net (code "82") (name "VCC_3V3") (class "Default")
      (node (ref "C1") (pin "2") (pinfunction "2_2") (pintype "passive"))
      (node (ref "C15") (pin "2") (pinfunction "2_2") (pintype "passive"))
      (node (ref "C17") (pin "2") (pinfunction "2_2") (pintype "passive"))
      (node (ref "C18") (pin "2") (pinfunction "2_2") (pintype "passive"))
      (node (ref "C19") (pin "2") (pinfunction "2_2") (pintype "passive"))
      (node (ref "C2") (pin "2") (pinfunction "2_2") (pintype "passive"))
      (node (ref "C20") (pin "2") (pinfunction "2_2") (pintype "passive"))
      (node (ref "C21") (pin "2") (pinfunction "2_2") (pintype "passive"))
      (node (ref "C22") (pin "2") (pinfunction "2_2") (pintype "passive"))
      (node (ref "C23") (pin "2") (pinfunction "2_2") (pintype "passive"))
      (node (ref "C24") (pin "2") (pinfunction "2_2") (pintype "passive"))
      (node (ref "H1") (pin "1") (pinfunction "1_1") (pintype "passive"))
      (node (ref "J1") (pin "2") (pinfunction "2_2") (pintype "passive"))
      (node (ref "L1") (pin "1") (pinfunction "1_1") (pintype "passive"))
      (node (ref "P1") (pin "1") (pinfunction "1_1") (pintype "passive"))
      (node (ref "Q1") (pin "2") (pinfunction "S_2") (pintype "passive"))
      (node (ref "R11") (pin "2") (pinfunction "2_2") (pintype "passive"))
      (node (ref "R12") (pin "1") (pinfunction "1_1") (pintype "passive"))
      (node (ref "R14") (pin "2") (pinfunction "2_2") (pintype "passive"))
      (node (ref "R15") (pin "2") (pinfunction "2_2") (pintype "passive"))
      (node (ref "R16") (pin "2") (pinfunction "2_2") (pintype "passive"))
      (node (ref "R18") (pin "2") (pinfunction "2_2") (pintype "passive"))
      (node (ref "R19") (pin "2") (pinfunction "2_2") (pintype "passive"))
      (node (ref "R2") (pin "2") (pinfunction "2_2") (pintype "passive"))
      (node (ref "R20") (pin "1") (pinfunction "1_1") (pintype "passive"))
      (node (ref "R3") (pin "2") (pinfunction "2_2") (pintype "passive"))
      (node (ref "R4") (pin "2") (pinfunction "2_2") (pintype "passive"))
      (node (ref "R5") (pin "1") (pinfunction "1_1") (pintype "passive"))
      (node (ref "R6") (pin "2") (pinfunction "2_2") (pintype "passive"))
      (node (ref "R7") (pin "2") (pinfunction "2_2") (pintype "passive"))
      (node (ref "R8") (pin "2") (pinfunction "2_2") (pintype "passive"))
      (node (ref "R9") (pin "2") (pinfunction "2_2") (pintype "passive"))
      (node (ref "TF1") (pin "4") (pinfunction "VDD_4") (pintype "passive"))
      (node (ref "U1") (pin "8") (pinfunction "VCC_8") (pintype "passive"))
      (node (ref "U4") (pin "100") (pinfunction "VDD_100") (pintype "passive"))
      (node (ref "U4") (pin "11") (pinfunction "VDD_11") (pintype "passive"))
      (node (ref "U4") (pin "19") (pinfunction "VDD_19") (pintype "passive"))
      (node (ref "U4") (pin "22") (pinfunction "VDDA_22") (pintype "passive"))
      (node (ref "U4") (pin "28") (pinfunction "VDD_28") (pintype "passive"))
      (node (ref "U4") (pin "50") (pinfunction "VDD_50") (pintype "passive"))
      (node (ref "U4") (pin "75") (pinfunction "VDD_75") (pintype "passive"))
      (node (ref "U7") (pin "1") (pinfunction "VCC_1") (pintype "passive"))
    )
    (net (code "83") (name "unconnected-(J1-Pad15)") (class "Default")
      (node (ref "J1") (pin "15") (pinfunction "15_15") (pintype "passive"))
    )
    (net (code "84") (name "unconnected-(J3-Pad5)") (class "Default")
      (node (ref "J3") (pin "5") (pintype "passive+no_connect"))
    )
    (net (code "85") (name "unconnected-(SW1-Pad3)") (class "Default")
      (node (ref "SW1") (pin "3") (pinfunction "3_3") (pintype "passive"))
    )
    (net (code "86") (name "unconnected-(SW2-Pad3)") (class "Default")
      (node (ref "SW2") (pin "3") (pinfunction "3_3") (pintype "passive"))
    )
    (net (code "87") (name "unconnected-(SW3-Pad3)") (class "Default")
      (node (ref "SW3") (pin "3") (pinfunction "3_3") (pintype "passive"))
    )
    (net (code "88") (name "unconnected-(SW4-Pad3)") (class "Default")
      (node (ref "SW4") (pin "3") (pinfunction "3_3") (pintype "passive"))
    )
    (net (code "89") (name "unconnected-(U2-DIO2-Pad7)") (class "Default")
      (node (ref "U2") (pin "7") (pinfunction "DIO2_7") (pintype "passive"))
    )
    (net (code "90") (name "unconnected-(U2-DIO3-Pad8)") (class "Default")
      (node (ref "U2") (pin "8") (pinfunction "DIO3_8") (pintype "passive"))
    )
    (net (code "91") (name "unconnected-(U2-DIO4-Pad10)") (class "Default")
      (node (ref "U2") (pin "10") (pinfunction "DIO4_10") (pintype "passive"))
    )
    (net (code "92") (name "unconnected-(U2-DIO5-Pad11)") (class "Default")
      (node (ref "U2") (pin "11") (pinfunction "DIO5_11") (pintype "passive"))
    )
    (net (code "93") (name "unconnected-(U4-PB2-Pad37)") (class "Default")
      (node (ref "U4") (pin "37") (pinfunction "PB2_37") (pintype "passive"))
    )
    (net (code "94") (name "unconnected-(U4-PB3-Pad89)") (class "Default")
      (node (ref "U4") (pin "89") (pinfunction "PB3_89") (pintype "passive"))
    )
    (net (code "95") (name "unconnected-(U4-PB4-Pad90)") (class "Default")
      (node (ref "U4") (pin "90") (pinfunction "PB4_90") (pintype "passive"))
    )
    (net (code "96") (name "unconnected-(U4-PB5-Pad91)") (class "Default")
      (node (ref "U4") (pin "91") (pinfunction "PB5_91") (pintype "passive"))
    )
    (net (code "97") (name "unconnected-(U4-PB6-Pad92)") (class "Default")
      (node (ref "U4") (pin "92") (pinfunction "PB6_92") (pintype "passive"))
    )
    (net (code "98") (name "unconnected-(U4-PB7-Pad93)") (class "Default")
      (node (ref "U4") (pin "93") (pinfunction "PB7_93") (pintype "passive"))
    )
    (net (code "99") (name "unconnected-(U4-PB8-Pad95)") (class "Default")
      (node (ref "U4") (pin "95") (pinfunction "PB8_95") (pintype "passive"))
    )
    (net (code "100") (name "unconnected-(U4-PB9-Pad96)") (class "Default")
      (node (ref "U4") (pin "96") (pinfunction "PB9_96") (pintype "passive"))
    )
    (net (code "101") (name "unconnected-(U4-PC0-Pad15)") (class "Default")
      (node (ref "U4") (pin "15") (pinfunction "PC0_15") (pintype "passive"))
    )
    (net (code "102") (name "unconnected-(U4-PC1-Pad16)") (class "Default")
      (node (ref "U4") (pin "16") (pinfunction "PC1_16") (pintype "passive"))
    )
    (net (code "103") (name "unconnected-(U4-PC2-Pad17)") (class "Default")
      (node (ref "U4") (pin "17") (pinfunction "PC2_17") (pintype "passive"))
    )
    (net (code "104") (name "unconnected-(U4-PC3-Pad18)") (class "Default")
      (node (ref "U4") (pin "18") (pinfunction "PC3_18") (pintype "passive"))
    )
    (net (code "105") (name "unconnected-(U4-PC4-Pad33)") (class "Default")
      (node (ref "U4") (pin "33") (pinfunction "PC4_33") (pintype "passive"))
    )
    (net (code "106") (name "unconnected-(U4-PC5-Pad34)") (class "Default")
      (node (ref "U4") (pin "34") (pinfunction "PC5_34") (pintype "passive"))
    )
    (net (code "107") (name "unconnected-(U4-PC13-Pad7)") (class "Default")
      (node (ref "U4") (pin "7") (pinfunction "PC13_7") (pintype "passive"))
    )
    (net (code "108") (name "unconnected-(U4-PE0-Pad97)") (class "Default")
      (node (ref "U4") (pin "97") (pinfunction "PE0_97") (pintype "passive"))
    )
    (net (code "109") (name "unconnected-(U4-PE1-Pad98)") (class "Default")
      (node (ref "U4") (pin "98") (pinfunction "PE1_98") (pintype "passive"))
    )
    (net (code "110") (name "unconnected-(U4-PE2-Pad1)") (class "Default")
      (node (ref "U4") (pin "1") (pinfunction "PE2_1") (pintype "passive"))
    )
    (net (code "111") (name "unconnected-(U4-PE3-Pad2)") (class "Default")
      (node (ref "U4") (pin "2") (pinfunction "PE3_2") (pintype "passive"))
    )
    (net (code "112") (name "unconnected-(U4-PE4-Pad3)") (class "Default")
      (node (ref "U4") (pin "3") (pinfunction "PE4_3") (pintype "passive"))
    )
    (net (code "113") (name "unconnected-(U4-PE5-Pad4)") (class "Default")
      (node (ref "U4") (pin "4") (pinfunction "PE5_4") (pintype "passive"))
    )
    (net (code "114") (name "unconnected-(U4-PE11-Pad42)") (class "Default")
      (node (ref "U4") (pin "42") (pinfunction "PE11_42") (pintype "passive"))
    )
    (net (code "115") (name "unconnected-(U4-PE12-Pad43)") (class "Default")
      (node (ref "U4") (pin "43") (pinfunction "PE12_43") (pintype "passive"))
    )
    (net (code "116") (name "unconnected-(U4-PE13-Pad44)") (class "Default")
      (node (ref "U4") (pin "44") (pinfunction "PE13_44") (pintype "passive"))
    )
    (net (code "117") (name "unconnected-(U4-PE15-Pad46)") (class "Default")
      (node (ref "U4") (pin "46") (pinfunction "PE15_46") (pintype "passive"))
    )
    (net (code "118") (name "unconnected-(U4-VREF+-Pad21)") (class "Default")
      (node (ref "U4") (pin "21") (pinfunction "VREF+_21") (pintype "passive"))
    )
    (net (code "119") (name "unconnected-(U8-BAT-Pad6)") (class "Default")
      (node (ref "U8") (pin "6") (pinfunction "BAT_6") (pintype "passive"))
    )
    (net (code "120") (name "unconnected-(U8-BOOT-Pad12)") (class "Default")
      (node (ref "U8") (pin "12") (pinfunction "BOOT_12") (pintype "passive"))
    )
    (net (code "121") (name "unconnected-(U8-LED-Pad11)") (class "Default")
      (node (ref "U8") (pin "11") (pinfunction "LED_11") (pintype "passive"))
    )
  )
)
